# aprs-wx.net
KiCad netlist of a schematic drawn in EAGLE
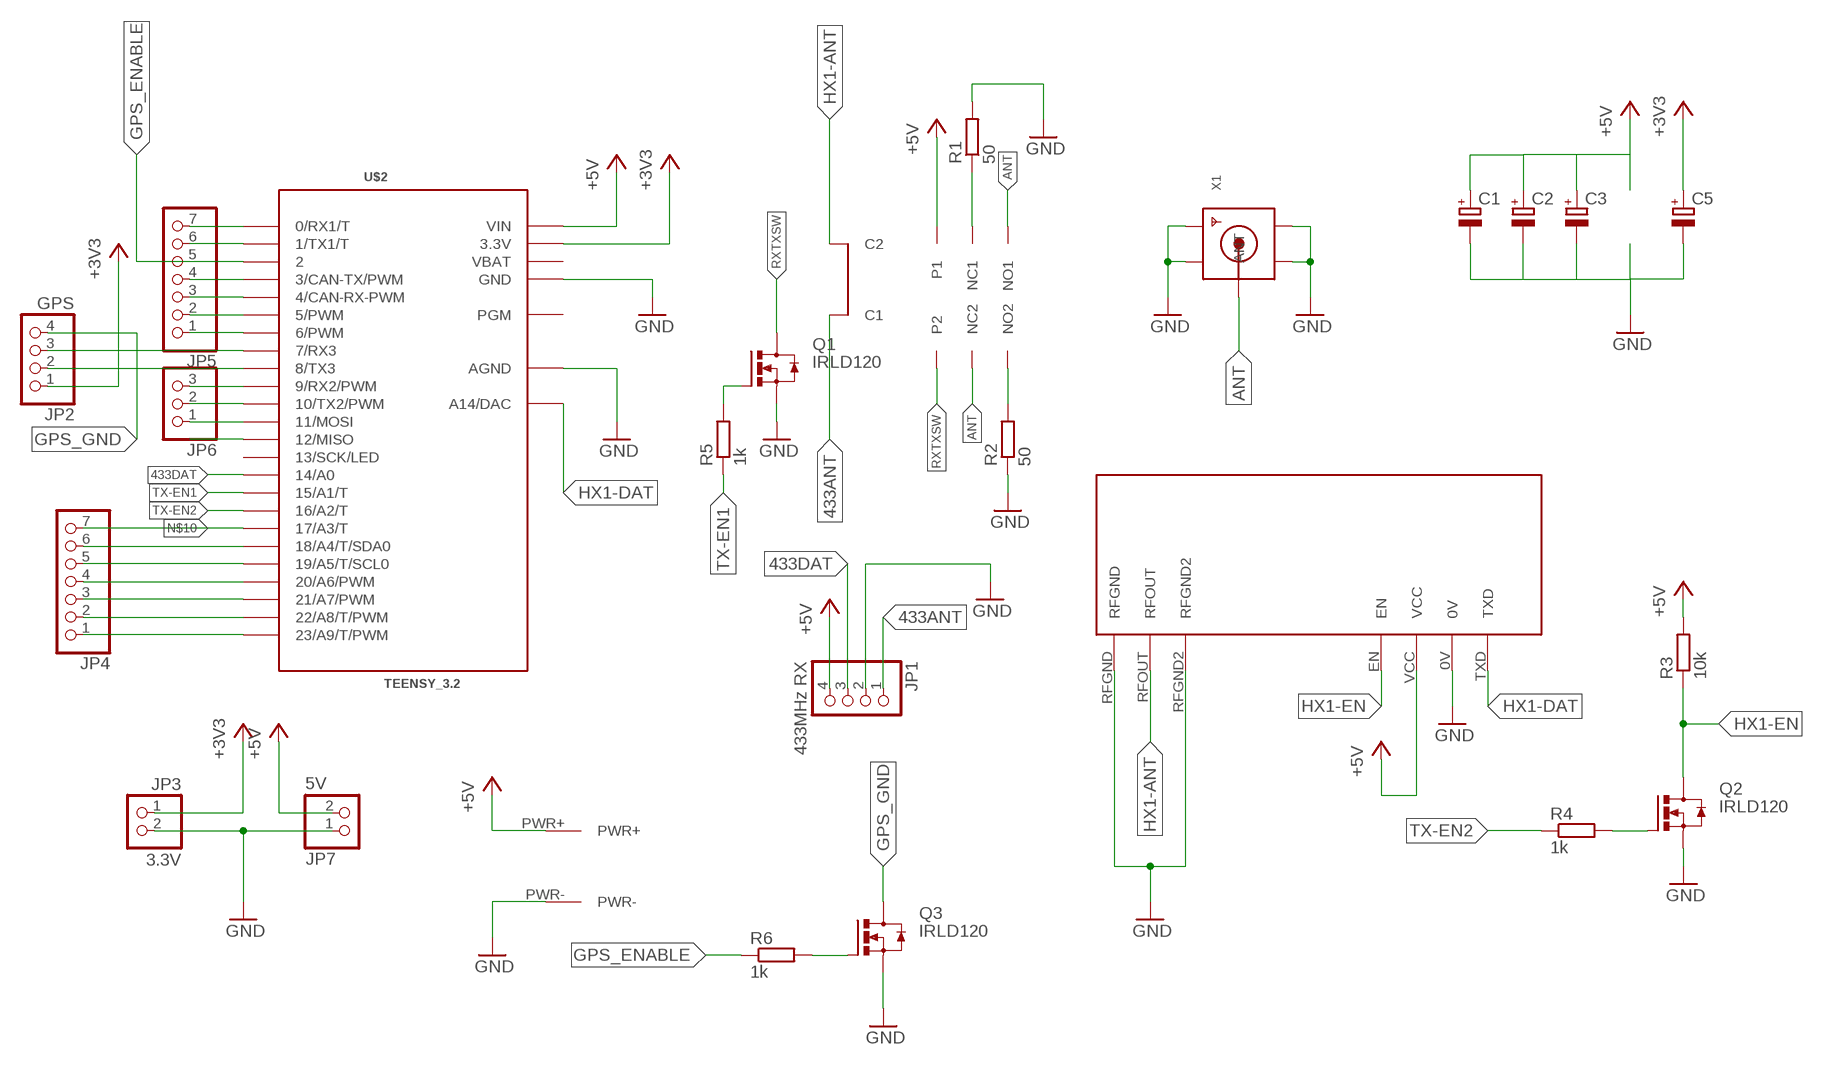
[diagram p0: schematic, sheet 1]

(export (version "E")
  (design (tool "Eeschema 10.0.6"))
  (components
    (comp (ref "BTPL1")
      (value "GS-SH-2XXT5V")
      (footprint "eagle-import:GOODSKY_RELAY")
      (libsource (lib "eagle-import") (part "GS-SH-2XXT5V"))
    )
    (comp (ref "C1")
      (value "CPOL-EUE2,5-6E")
      (footprint "eagle-import:E2,5-6E")
      (libsource (lib "eagle-import") (part "CPOL-EUE2,5-6E"))
    )
    (comp (ref "C2")
      (value "CPOL-EUE2,5-6E")
      (footprint "eagle-import:E2,5-6E")
      (libsource (lib "eagle-import") (part "CPOL-EUE2,5-6E"))
    )
    (comp (ref "C3")
      (value "CPOL-EUE2,5-6E")
      (footprint "eagle-import:E2,5-6E")
      (libsource (lib "eagle-import") (part "CPOL-EUE2,5-6E"))
    )
    (comp (ref "C5")
      (value "CPOL-EUE2,5-6E")
      (footprint "eagle-import:E2,5-6E")
      (libsource (lib "eagle-import") (part "CPOL-EUE2,5-6E"))
    )
    (comp (ref "JP1")
      (value "433MHz RX")
      (footprint "eagle-import:1X04")
      (libsource (lib "eagle-import") (part "PINHD-1X4"))
    )
    (comp (ref "JP2")
      (value "GPS")
      (footprint "eagle-import:1X04")
      (libsource (lib "eagle-import") (part "PINHD-1X4"))
    )
    (comp (ref "JP3")
      (value "3.3V")
      (footprint "eagle-import:1X02")
      (libsource (lib "eagle-import") (part "PINHD-1X2"))
    )
    (comp (ref "JP4")
      (value "PINHD-1X7")
      (footprint "eagle-import:1X07")
      (libsource (lib "eagle-import") (part "PINHD-1X7"))
    )
    (comp (ref "JP5")
      (value "PINHD-1X7")
      (footprint "eagle-import:1X07")
      (libsource (lib "eagle-import") (part "PINHD-1X7"))
    )
    (comp (ref "JP6")
      (value "PINHD-1X3")
      (footprint "eagle-import:1X03")
      (libsource (lib "eagle-import") (part "PINHD-1X3"))
    )
    (comp (ref "JP7")
      (value "5V")
      (footprint "eagle-import:1X02")
      (libsource (lib "eagle-import") (part "PINHD-1X2"))
    )
    (comp (ref "Q1")
      (value "IRLD120")
      (footprint "eagle-import:HVMDIP")
      (libsource (lib "eagle-import") (part "IRLD120"))
    )
    (comp (ref "Q2")
      (value "IRLD120")
      (footprint "eagle-import:HVMDIP")
      (libsource (lib "eagle-import") (part "IRLD120"))
    )
    (comp (ref "Q3")
      (value "IRLD120")
      (footprint "eagle-import:HVMDIP")
      (libsource (lib "eagle-import") (part "IRLD120"))
    )
    (comp (ref "R1")
      (value "50")
      (footprint "eagle-import:0207_10")
      (libsource (lib "eagle-import") (part "R-EU_0207/10"))
    )
    (comp (ref "R2")
      (value "50")
      (footprint "eagle-import:0207_10")
      (libsource (lib "eagle-import") (part "R-EU_0207/10"))
    )
    (comp (ref "R3")
      (value "10k")
      (footprint "eagle-import:0207_10")
      (libsource (lib "eagle-import") (part "R-EU_0207/10"))
    )
    (comp (ref "R4")
      (value "1k")
      (footprint "eagle-import:0207_10")
      (libsource (lib "eagle-import") (part "R-EU_0207/10"))
    )
    (comp (ref "R5")
      (value "1k")
      (footprint "eagle-import:0207_10")
      (libsource (lib "eagle-import") (part "R-EU_0207/10"))
    )
    (comp (ref "R6")
      (value "1k")
      (footprint "eagle-import:0207_10")
      (libsource (lib "eagle-import") (part "R-EU_0207/10"))
    )
    (comp (ref "U$1")
      (value "RADIOMETRIX-HX1")
      (footprint "eagle-import:RADIOMETRIX-HX1")
      (libsource (lib "eagle-import") (part "RADIOMETRIX-HX1"))
    )
    (comp (ref "U$2")
      (value "TEENSY_3.2")
      (footprint "eagle-import:TEENSY_3.0-3.2&LC_OUTER_ROW")
      (libsource (lib "eagle-import") (part "TEENSY_3.1-3.2_OUTER_ROW"))
    )
    (comp (ref "U$3")
      (value "SOLDERPWR-1")
      (footprint "eagle-import:SOLDERPWR-1")
      (libsource (lib "eagle-import") (part "SOLDERPWR-1"))
    )
    (comp (ref "X1")
      (value "SMACONNECTOR_EDGE")
      (footprint "eagle-import:SMA_EDGELAUNCH")
      (libsource (lib "eagle-import") (part "SMACONNECTOR_EDGE"))
    )
  )
  (nets
    (net (code "1") (name "+3V3") (class "Default")
      (node (ref "C5") (pin "+") (pinfunction "+_+") (pintype "passive"))
      (node (ref "JP2") (pin "1") (pinfunction "1_1") (pintype "passive"))
      (node (ref "JP3") (pin "1") (pinfunction "1_1") (pintype "passive"))
      (node (ref "U$2") (pin "3.3V") (pinfunction "3.3V_3.3V") (pintype "power_in"))
      (node (ref "U$2") (pin "3.3V1") (pinfunction "3.3V_3.3V1") (pintype "power_in"))
    )
    (net (code "2") (name "+5V") (class "Default")
      (node (ref "BTPL1") (pin "C2") (pinfunction "P1_C2") (pintype "bidirectional"))
      (node (ref "C1") (pin "+") (pinfunction "+_+") (pintype "passive"))
      (node (ref "C2") (pin "+") (pinfunction "+_+") (pintype "passive"))
      (node (ref "C3") (pin "+") (pinfunction "+_+") (pintype "passive"))
      (node (ref "JP1") (pin "4") (pinfunction "4_4") (pintype "passive"))
      (node (ref "JP7") (pin "2") (pinfunction "2_2") (pintype "passive"))
      (node (ref "R3") (pin "2") (pinfunction "2_2") (pintype "passive"))
      (node (ref "U$1") (pin "VCC") (pinfunction "VCC_VCC") (pintype "bidirectional"))
      (node (ref "U$2") (pin "VIN") (pinfunction "VIN_VIN") (pintype "power_in"))
      (node (ref "U$3") (pin "PWR+") (pinfunction "PWR+_PWR+") (pintype "power_in"))
    )
    (net (code "3") (name "/VBAT") (class "Default")
      (node (ref "U$2") (pin "VBAT") (pinfunction "VBAT_VBAT") (pintype "power_in"))
    )
    (net (code "4") (name "433ANT") (class "Default")
      (node (ref "BTPL1") (pin "P2") (pinfunction "C1_P2") (pintype "bidirectional"))
      (node (ref "JP1") (pin "1") (pinfunction "1_1") (pintype "passive"))
    )
    (net (code "5") (name "433DAT") (class "Default")
      (node (ref "JP1") (pin "3") (pinfunction "3_3") (pintype "passive"))
      (node (ref "U$2") (pin "14/A0") (pinfunction "14/A0_14/A0") (pintype "bidirectional"))
    )
    (net (code "6") (name "ANT") (class "Default")
      (node (ref "BTPL1") (pin "NC2") (pinfunction "NO1_NC2") (pintype "output"))
      (node (ref "BTPL1") (pin "NO1") (pinfunction "NC2_NO1") (pintype "output"))
      (node (ref "X1") (pin "P") (pinfunction "ANT_P") (pintype "bidirectional"))
    )
    (net (code "7") (name "GND") (class "Default")
      (node (ref "C1") (pin "-") (pinfunction "-_-") (pintype "passive"))
      (node (ref "C2") (pin "-") (pinfunction "-_-") (pintype "passive"))
      (node (ref "C3") (pin "-") (pinfunction "-_-") (pintype "passive"))
      (node (ref "C5") (pin "-") (pinfunction "-_-") (pintype "passive"))
      (node (ref "JP1") (pin "2") (pinfunction "2_2") (pintype "passive"))
      (node (ref "JP3") (pin "2") (pinfunction "2_2") (pintype "passive"))
      (node (ref "JP7") (pin "1") (pinfunction "1_1") (pintype "passive"))
      (node (ref "Q1") (pin "S") (pinfunction "S_S") (pintype "passive"))
      (node (ref "Q2") (pin "S") (pinfunction "S_S") (pintype "passive"))
      (node (ref "Q3") (pin "S") (pinfunction "S_S") (pintype "passive"))
      (node (ref "R1") (pin "2") (pinfunction "2_2") (pintype "passive"))
      (node (ref "R2") (pin "1") (pinfunction "1_1") (pintype "passive"))
      (node (ref "U$1") (pin "0V") (pinfunction "0V_0V") (pintype "bidirectional"))
      (node (ref "U$1") (pin "RFGND") (pinfunction "RFGND_RFGND") (pintype "bidirectional"))
      (node (ref "U$1") (pin "RFGND2") (pinfunction "RFGND2_RFGND2") (pintype "bidirectional"))
      (node (ref "U$2") (pin "AGND") (pinfunction "AGND_AGND") (pintype "power_in"))
      (node (ref "U$2") (pin "GND") (pinfunction "GND_GND") (pintype "power_in"))
      (node (ref "U$2") (pin "GND1") (pinfunction "GND_GND1") (pintype "power_in"))
      (node (ref "U$3") (pin "PWR-") (pinfunction "PWR-_PWR-") (pintype "power_in"))
      (node (ref "X1") (pin "GND@1") (pinfunction "GND4_GND@1") (pintype "power_in"))
      (node (ref "X1") (pin "GND@2") (pinfunction "GND3_GND@2") (pintype "power_in"))
      (node (ref "X1") (pin "GND@3") (pinfunction "GND2_GND@3") (pintype "power_in"))
      (node (ref "X1") (pin "GND@4") (pinfunction "GND1_GND@4") (pintype "power_in"))
    )
    (net (code "8") (name "GPS_ENABLE") (class "Default")
      (node (ref "JP5") (pin "5") (pinfunction "5_5") (pintype "passive"))
      (node (ref "R6") (pin "1") (pinfunction "1_1") (pintype "passive"))
      (node (ref "U$2") (pin "2") (pinfunction "2_2") (pintype "bidirectional"))
    )
    (net (code "9") (name "GPS_GND") (class "Default")
      (node (ref "JP2") (pin "4") (pinfunction "4_4") (pintype "passive"))
      (node (ref "Q3") (pin "D@1") (pinfunction "D_D@1") (pintype "passive"))
      (node (ref "Q3") (pin "D@2") (pinfunction "D_D@2") (pintype "passive"))
    )
    (net (code "10") (name "HX1-ANT") (class "Default")
      (node (ref "BTPL1") (pin "P1") (pinfunction "C2_P1") (pintype "bidirectional"))
      (node (ref "U$1") (pin "RFOUT") (pinfunction "RFOUT_RFOUT") (pintype "bidirectional"))
    )
    (net (code "11") (name "HX1-DAT") (class "Default")
      (node (ref "U$1") (pin "TXD") (pinfunction "TXD_TXD") (pintype "bidirectional"))
      (node (ref "U$2") (pin "RESET/DAC") (pinfunction "A14/DAC_RESET/DAC") (pintype "bidirectional"))
    )
    (net (code "12") (name "HX1-EN") (class "Default")
      (node (ref "Q2") (pin "D@1") (pinfunction "D_D@1") (pintype "passive"))
      (node (ref "Q2") (pin "D@2") (pinfunction "D_D@2") (pintype "passive"))
      (node (ref "R3") (pin "1") (pinfunction "1_1") (pintype "passive"))
      (node (ref "U$1") (pin "EN") (pinfunction "EN_EN") (pintype "bidirectional"))
    )
    (net (code "13") (name "N$10") (class "Default")
      (node (ref "JP4") (pin "7") (pinfunction "7_7") (pintype "passive"))
      (node (ref "U$2") (pin "17/A3") (pinfunction "17/A3/T_17/A3") (pintype "bidirectional"))
    )
    (net (code "14") (name "Net-(BTPL1-NC1)") (class "Default")
      (node (ref "BTPL1") (pin "NO2") (pinfunction "NC1_NO2") (pintype "output"))
      (node (ref "R1") (pin "1") (pinfunction "1_1") (pintype "passive"))
    )
    (net (code "15") (name "Net-(BTPL1-NO2)") (class "Default")
      (node (ref "BTPL1") (pin "NC1") (pinfunction "NO2_NC1") (pintype "output"))
      (node (ref "R2") (pin "2") (pinfunction "2_2") (pintype "passive"))
    )
    (net (code "16") (name "Net-(Q1-PadG)") (class "Default")
      (node (ref "Q1") (pin "G") (pinfunction "G_G") (pintype "passive"))
      (node (ref "R5") (pin "2") (pinfunction "2_2") (pintype "passive"))
    )
    (net (code "17") (name "Net-(Q2-PadG)") (class "Default")
      (node (ref "Q2") (pin "G") (pinfunction "G_G") (pintype "passive"))
      (node (ref "R4") (pin "2") (pinfunction "2_2") (pintype "passive"))
    )
    (net (code "18") (name "Net-(Q3-PadG)") (class "Default")
      (node (ref "Q3") (pin "G") (pinfunction "G_G") (pintype "passive"))
      (node (ref "R6") (pin "2") (pinfunction "2_2") (pintype "passive"))
    )
    (net (code "19") (name "Net-(U$2-0{slash}RX1{slash}T)") (class "Default")
      (node (ref "JP5") (pin "7") (pinfunction "7_7") (pintype "passive"))
      (node (ref "U$2") (pin "0") (pinfunction "0/RX1/T_0") (pintype "bidirectional"))
    )
    (net (code "20") (name "Net-(U$2-1{slash}TX1{slash}T)") (class "Default")
      (node (ref "JP5") (pin "6") (pinfunction "6_6") (pintype "passive"))
      (node (ref "U$2") (pin "1") (pinfunction "1/TX1/T_1") (pintype "bidirectional"))
    )
    (net (code "21") (name "Net-(U$2-3{slash}CAN-TX{slash}PWM)") (class "Default")
      (node (ref "JP5") (pin "4") (pinfunction "4_4") (pintype "passive"))
      (node (ref "U$2") (pin "3") (pinfunction "3/CAN-TX/PWM_3") (pintype "bidirectional"))
    )
    (net (code "22") (name "Net-(U$2-4{slash}CAN-RX-PWM)") (class "Default")
      (node (ref "JP5") (pin "3") (pinfunction "3_3") (pintype "passive"))
      (node (ref "U$2") (pin "4") (pinfunction "4/CAN-RX-PWM_4") (pintype "bidirectional"))
    )
    (net (code "23") (name "Net-(U$2-5{slash}PWM)") (class "Default")
      (node (ref "JP5") (pin "2") (pinfunction "2_2") (pintype "passive"))
      (node (ref "U$2") (pin "5") (pinfunction "5/PWM_5") (pintype "bidirectional"))
    )
    (net (code "24") (name "Net-(U$2-6{slash}PWM)") (class "Default")
      (node (ref "JP5") (pin "1") (pinfunction "1_1") (pintype "passive"))
      (node (ref "U$2") (pin "6") (pinfunction "6/PWM_6") (pintype "bidirectional"))
    )
    (net (code "25") (name "Net-(U$2-7{slash}RX3)") (class "Default")
      (node (ref "JP2") (pin "3") (pinfunction "3_3") (pintype "passive"))
      (node (ref "U$2") (pin "7") (pinfunction "7/RX3_7") (pintype "bidirectional"))
    )
    (net (code "26") (name "Net-(U$2-8{slash}TX3)") (class "Default")
      (node (ref "JP2") (pin "2") (pinfunction "2_2") (pintype "passive"))
      (node (ref "U$2") (pin "8") (pinfunction "8/TX3_8") (pintype "bidirectional"))
    )
    (net (code "27") (name "Net-(U$2-9{slash}RX2{slash}PWM)") (class "Default")
      (node (ref "JP6") (pin "3") (pinfunction "3_3") (pintype "passive"))
      (node (ref "U$2") (pin "9") (pinfunction "9/RX2/PWM_9") (pintype "bidirectional"))
    )
    (net (code "28") (name "Net-(U$2-10{slash}TX2{slash}PWM)") (class "Default")
      (node (ref "JP6") (pin "2") (pinfunction "2_2") (pintype "passive"))
      (node (ref "U$2") (pin "10") (pinfunction "10/TX2/PWM_10") (pintype "bidirectional"))
    )
    (net (code "29") (name "Net-(U$2-11{slash}MOSI)") (class "Default")
      (node (ref "JP6") (pin "1") (pinfunction "1_1") (pintype "passive"))
      (node (ref "U$2") (pin "11") (pinfunction "11/MOSI_11") (pintype "bidirectional"))
    )
    (net (code "30") (name "Net-(U$2-18{slash}A4{slash}T{slash}SDA0)") (class "Default")
      (node (ref "JP4") (pin "6") (pinfunction "6_6") (pintype "passive"))
      (node (ref "U$2") (pin "18/A4") (pinfunction "18/A4/T/SDA0_18/A4") (pintype "bidirectional"))
    )
    (net (code "31") (name "Net-(U$2-19{slash}A5{slash}T{slash}SCL0)") (class "Default")
      (node (ref "JP4") (pin "5") (pinfunction "5_5") (pintype "passive"))
      (node (ref "U$2") (pin "19/A5") (pinfunction "19/A5/T/SCL0_19/A5") (pintype "bidirectional"))
    )
    (net (code "32") (name "Net-(U$2-20{slash}A6{slash}PWM)") (class "Default")
      (node (ref "JP4") (pin "4") (pinfunction "4_4") (pintype "passive"))
      (node (ref "U$2") (pin "20/A6") (pinfunction "20/A6/PWM_20/A6") (pintype "bidirectional"))
    )
    (net (code "33") (name "Net-(U$2-21{slash}A7{slash}PWM)") (class "Default")
      (node (ref "JP4") (pin "3") (pinfunction "3_3") (pintype "passive"))
      (node (ref "U$2") (pin "21/A7") (pinfunction "21/A7/PWM_21/A7") (pintype "bidirectional"))
    )
    (net (code "34") (name "Net-(U$2-22{slash}A8{slash}T{slash}PWM)") (class "Default")
      (node (ref "JP4") (pin "2") (pinfunction "2_2") (pintype "passive"))
      (node (ref "U$2") (pin "22/A8") (pinfunction "22/A8/T/PWM_22/A8") (pintype "bidirectional"))
    )
    (net (code "35") (name "Net-(U$2-23{slash}A9{slash}T{slash}PWM)") (class "Default")
      (node (ref "JP4") (pin "1") (pinfunction "1_1") (pintype "passive"))
      (node (ref "U$2") (pin "23/A9") (pinfunction "23/A9/T/PWM_23/A9") (pintype "bidirectional"))
    )
    (net (code "36") (name "RXTXSW") (class "Default")
      (node (ref "BTPL1") (pin "C1") (pinfunction "P2_C1") (pintype "bidirectional"))
      (node (ref "Q1") (pin "D@1") (pinfunction "D_D@1") (pintype "passive"))
      (node (ref "Q1") (pin "D@2") (pinfunction "D_D@2") (pintype "passive"))
    )
    (net (code "37") (name "TX-EN1") (class "Default")
      (node (ref "R5") (pin "1") (pinfunction "1_1") (pintype "passive"))
      (node (ref "U$2") (pin "15/A1") (pinfunction "15/A1/T_15/A1") (pintype "bidirectional"))
    )
    (net (code "38") (name "TX-EN2") (class "Default")
      (node (ref "R4") (pin "1") (pinfunction "1_1") (pintype "passive"))
      (node (ref "U$2") (pin "16/A2") (pinfunction "16/A2/T_16/A2") (pintype "bidirectional"))
    )
    (net (code "39") (name "unconnected-(U$2-12{slash}MISO-Pad12)") (class "Default")
      (node (ref "U$2") (pin "12") (pinfunction "12/MISO_12") (pintype "bidirectional"))
    )
    (net (code "40") (name "unconnected-(U$2-13{slash}SCK{slash}LED-Pad13)") (class "Default")
      (node (ref "U$2") (pin "13") (pinfunction "13/SCK/LED_13") (pintype "bidirectional"))
    )
    (net (code "41") (name "unconnected-(U$2-PadPGM)") (class "Default")
      (node (ref "U$2") (pin "PGM") (pinfunction "PGM_PGM") (pintype "bidirectional"))
    )
  )
)
